# 2nd_layer.net
KiCad netlist of a schematic drawn in EAGLE
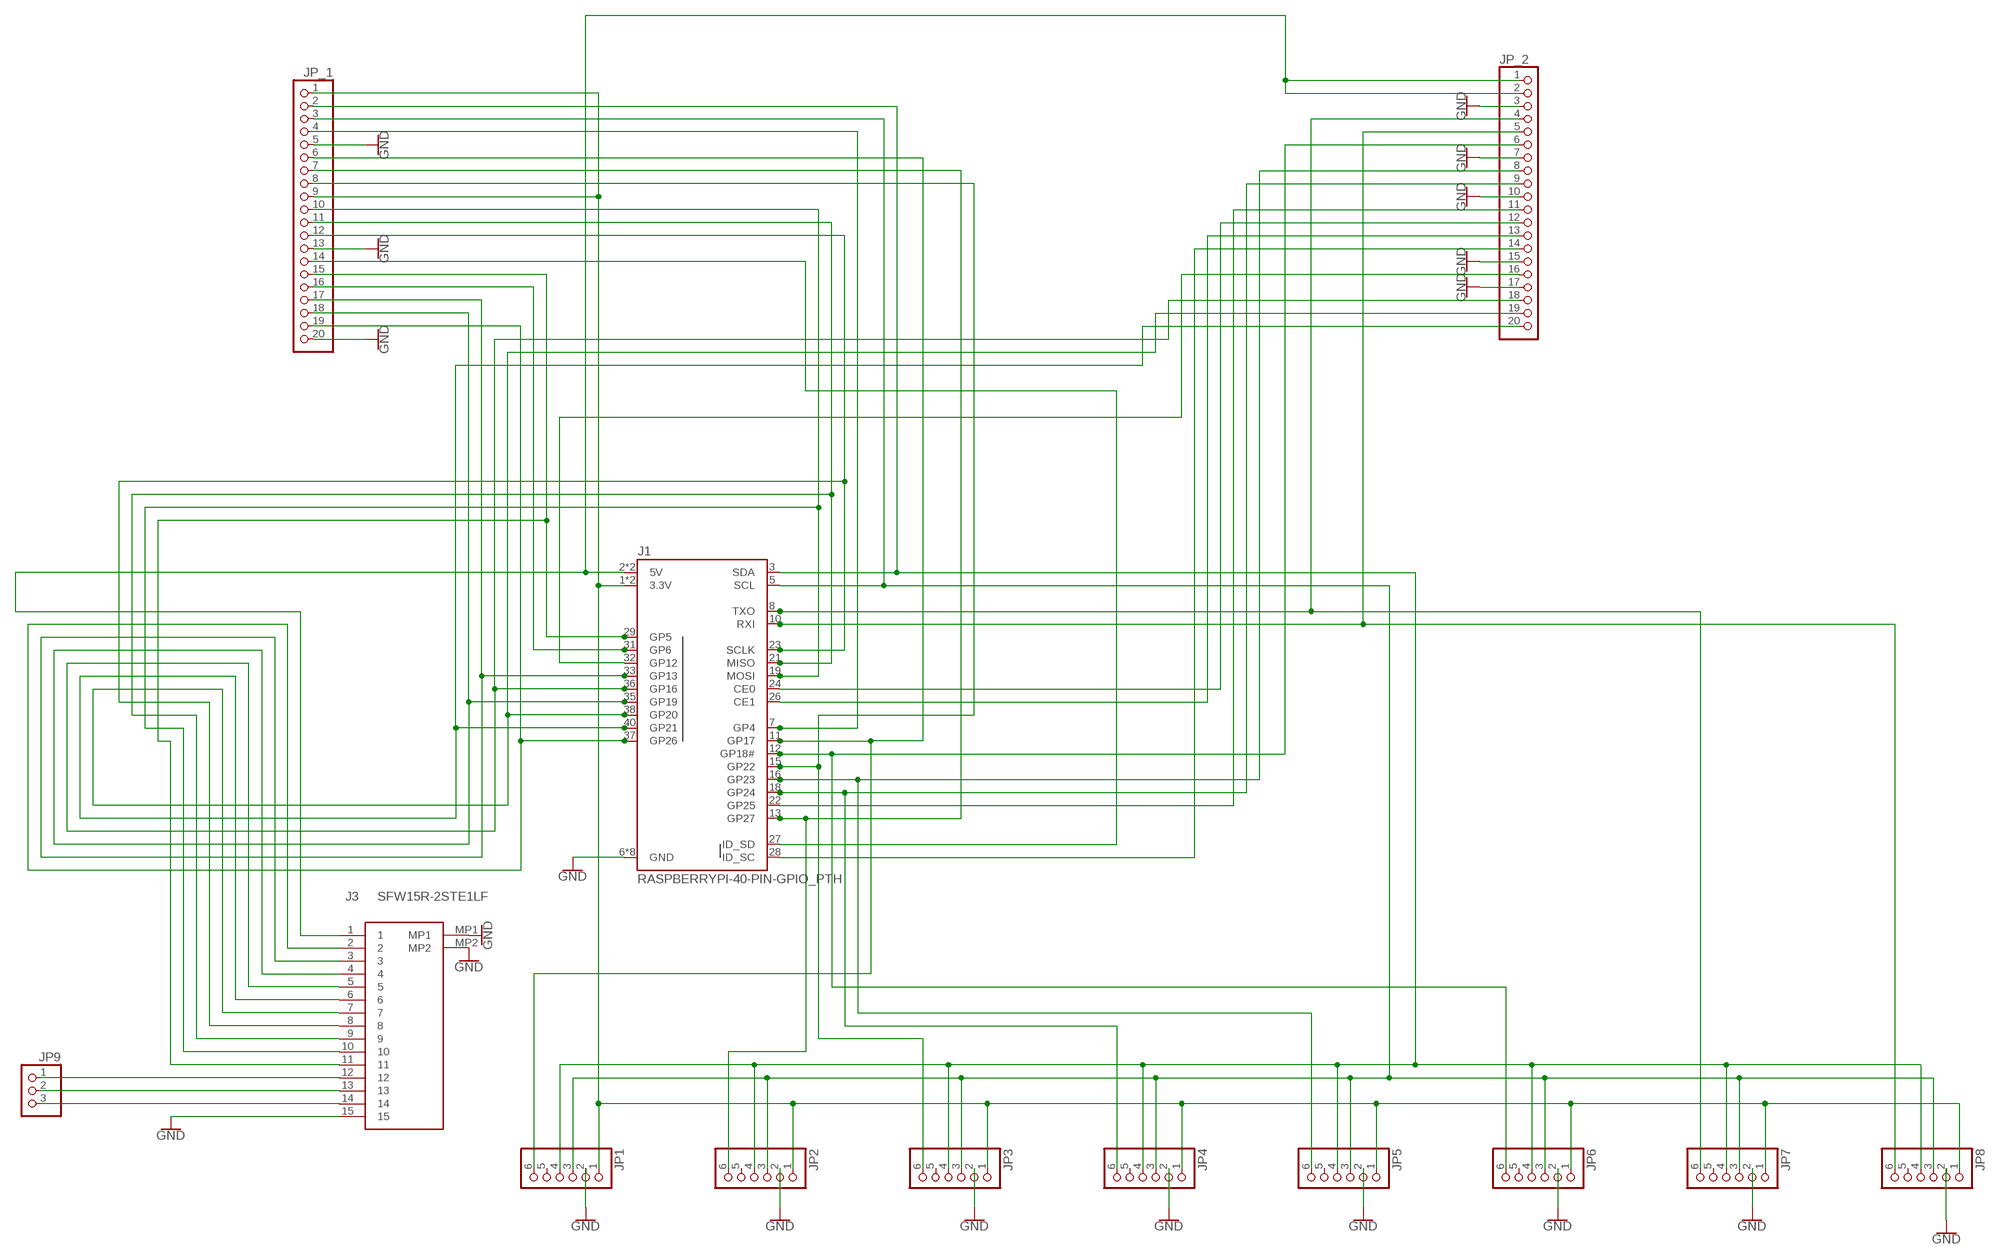
[diagram p0: schematic, sheet 1]

(export (version "E")
  (design (tool "Eeschema 10.0.6"))
  (components
    (comp (ref "J1")
      (value "RASPBERRYPI-40-PIN-GPIO_PTH")
      (footprint "eagle-import:2X20_SHROUDED")
      (libsource (lib "eagle-import") (part "RASPBERRYPI-40-PIN-GPIO_PTH"))
    )
    (comp (ref "J3")
      (value "SFW15R-2STE1LF")
      (footprint "eagle-import:SFW15R2STE1LF")
      (libsource (lib "eagle-import") (part "SFW15R-2STE1LF"))
    )
    (comp (ref "JP1")
      (value "PINHD-1X6")
      (footprint "eagle-import:1X06")
      (libsource (lib "eagle-import") (part "PINHD-1X6"))
    )
    (comp (ref "JP2")
      (value "PINHD-1X6")
      (footprint "eagle-import:1X06")
      (libsource (lib "eagle-import") (part "PINHD-1X6"))
    )
    (comp (ref "JP3")
      (value "PINHD-1X6")
      (footprint "eagle-import:1X06")
      (libsource (lib "eagle-import") (part "PINHD-1X6"))
    )
    (comp (ref "JP4")
      (value "PINHD-1X6")
      (footprint "eagle-import:1X06")
      (libsource (lib "eagle-import") (part "PINHD-1X6"))
    )
    (comp (ref "JP5")
      (value "PINHD-1X6")
      (footprint "eagle-import:1X06")
      (libsource (lib "eagle-import") (part "PINHD-1X6"))
    )
    (comp (ref "JP6")
      (value "PINHD-1X6")
      (footprint "eagle-import:1X06")
      (libsource (lib "eagle-import") (part "PINHD-1X6"))
    )
    (comp (ref "JP7")
      (value "PINHD-1X6")
      (footprint "eagle-import:1X06")
      (libsource (lib "eagle-import") (part "PINHD-1X6"))
    )
    (comp (ref "JP8")
      (value "PINHD-1X6")
      (footprint "eagle-import:1X06")
      (libsource (lib "eagle-import") (part "PINHD-1X6"))
    )
    (comp (ref "JP9")
      (value "PINHD-1X3")
      (footprint "eagle-import:1X03")
      (libsource (lib "eagle-import") (part "PINHD-1X3"))
    )
    (comp (ref "JP_1")
      (value "PINHD-1X20")
      (footprint "eagle-import:1X20")
      (libsource (lib "eagle-import") (part "PINHD-1X20"))
    )
    (comp (ref "JP_2")
      (value "PINHD-1X20")
      (footprint "eagle-import:1X20")
      (libsource (lib "eagle-import") (part "PINHD-1X20"))
    )
  )
  (nets
    (net (code "1") (name "GND") (class "Default")
      (node (ref "J1") (pin "14") (pinfunction "GND_14") (pintype "power_in"))
      (node (ref "J1") (pin "20") (pinfunction "GND_20") (pintype "power_in"))
      (node (ref "J1") (pin "25") (pinfunction "GND_25") (pintype "power_in"))
      (node (ref "J1") (pin "30") (pinfunction "GND_30") (pintype "power_in"))
      (node (ref "J1") (pin "34") (pinfunction "GND_34") (pintype "power_in"))
      (node (ref "J1") (pin "39") (pinfunction "GND_39") (pintype "power_in"))
      (node (ref "J1") (pin "6") (pinfunction "GND_6") (pintype "power_in"))
      (node (ref "J1") (pin "9") (pinfunction "GND_9") (pintype "power_in"))
      (node (ref "J3") (pin "15") (pinfunction "15_15") (pintype "bidirectional"))
      (node (ref "J3") (pin "MP1") (pinfunction "MP1_MP1") (pintype "bidirectional"))
      (node (ref "J3") (pin "MP2") (pinfunction "MP2_MP2") (pintype "bidirectional"))
      (node (ref "JP1") (pin "2") (pinfunction "2_2") (pintype "passive"))
      (node (ref "JP2") (pin "2") (pinfunction "2_2") (pintype "passive"))
      (node (ref "JP3") (pin "2") (pinfunction "2_2") (pintype "passive"))
      (node (ref "JP4") (pin "2") (pinfunction "2_2") (pintype "passive"))
      (node (ref "JP5") (pin "2") (pinfunction "2_2") (pintype "passive"))
      (node (ref "JP6") (pin "2") (pinfunction "2_2") (pintype "passive"))
      (node (ref "JP7") (pin "2") (pinfunction "2_2") (pintype "passive"))
      (node (ref "JP8") (pin "2") (pinfunction "2_2") (pintype "passive"))
      (node (ref "JP_1") (pin "13") (pinfunction "13_13") (pintype "passive"))
      (node (ref "JP_1") (pin "20") (pinfunction "20_20") (pintype "passive"))
      (node (ref "JP_1") (pin "5") (pinfunction "5_5") (pintype "passive"))
      (node (ref "JP_2") (pin "10") (pinfunction "10_10") (pintype "passive"))
      (node (ref "JP_2") (pin "15") (pinfunction "15_15") (pintype "passive"))
      (node (ref "JP_2") (pin "17") (pinfunction "17_17") (pintype "passive"))
      (node (ref "JP_2") (pin "3") (pinfunction "3_3") (pintype "passive"))
      (node (ref "JP_2") (pin "7") (pinfunction "7_7") (pintype "passive"))
    )
    (net (code "2") (name "Net-(J1-3.3V-Pad1)") (class "Default")
      (node (ref "J1") (pin "1") (pinfunction "3.3V_1") (pintype "power_in"))
      (node (ref "J1") (pin "17") (pinfunction "3.3V_17") (pintype "power_in"))
      (node (ref "JP1") (pin "1") (pinfunction "1_1") (pintype "passive"))
      (node (ref "JP2") (pin "1") (pinfunction "1_1") (pintype "passive"))
      (node (ref "JP3") (pin "1") (pinfunction "1_1") (pintype "passive"))
      (node (ref "JP4") (pin "1") (pinfunction "1_1") (pintype "passive"))
      (node (ref "JP5") (pin "1") (pinfunction "1_1") (pintype "passive"))
      (node (ref "JP6") (pin "1") (pinfunction "1_1") (pintype "passive"))
      (node (ref "JP7") (pin "1") (pinfunction "1_1") (pintype "passive"))
      (node (ref "JP8") (pin "1") (pinfunction "1_1") (pintype "passive"))
      (node (ref "JP_1") (pin "1") (pinfunction "1_1") (pintype "passive"))
      (node (ref "JP_1") (pin "9") (pinfunction "9_9") (pintype "passive"))
    )
    (net (code "3") (name "Net-(J1-5V-Pad2)") (class "Default")
      (node (ref "J1") (pin "2") (pinfunction "5V_2") (pintype "power_in"))
      (node (ref "J1") (pin "4") (pinfunction "5V_4") (pintype "power_in"))
      (node (ref "J3") (pin "1") (pinfunction "1_1") (pintype "bidirectional"))
      (node (ref "JP_2") (pin "1") (pinfunction "1_1") (pintype "passive"))
      (node (ref "JP_2") (pin "2") (pinfunction "2_2") (pintype "passive"))
    )
    (net (code "4") (name "Net-(J1-CE0)") (class "Default")
      (node (ref "J1") (pin "24") (pinfunction "CE0_24") (pintype "output"))
      (node (ref "JP_2") (pin "12") (pinfunction "12_12") (pintype "passive"))
    )
    (net (code "5") (name "Net-(J1-CE1)") (class "Default")
      (node (ref "J1") (pin "26") (pinfunction "CE1_26") (pintype "output"))
      (node (ref "JP_2") (pin "13") (pinfunction "13_13") (pintype "passive"))
    )
    (net (code "6") (name "Net-(J1-GP4)") (class "Default")
      (node (ref "J1") (pin "7") (pinfunction "GP4_7") (pintype "bidirectional"))
      (node (ref "JP_1") (pin "4") (pinfunction "4_4") (pintype "passive"))
    )
    (net (code "7") (name "Net-(J1-GP5)") (class "Default")
      (node (ref "J1") (pin "29") (pinfunction "GP5_29") (pintype "bidirectional"))
      (node (ref "J3") (pin "11") (pinfunction "11_11") (pintype "bidirectional"))
      (node (ref "JP_1") (pin "15") (pinfunction "15_15") (pintype "passive"))
    )
    (net (code "8") (name "Net-(J1-GP6)") (class "Default")
      (node (ref "J1") (pin "31") (pinfunction "GP6_31") (pintype "bidirectional"))
      (node (ref "JP_1") (pin "16") (pinfunction "16_16") (pintype "passive"))
    )
    (net (code "9") (name "Net-(J1-GP12)") (class "Default")
      (node (ref "J1") (pin "32") (pinfunction "GP12_32") (pintype "bidirectional"))
      (node (ref "JP_2") (pin "16") (pinfunction "16_16") (pintype "passive"))
    )
    (net (code "10") (name "Net-(J1-GP13)") (class "Default")
      (node (ref "J1") (pin "33") (pinfunction "GP13_33") (pintype "bidirectional"))
      (node (ref "J3") (pin "3") (pinfunction "3_3") (pintype "bidirectional"))
      (node (ref "JP_1") (pin "17") (pinfunction "17_17") (pintype "passive"))
    )
    (net (code "11") (name "Net-(J1-GP16)") (class "Default")
      (node (ref "J1") (pin "36") (pinfunction "GP16_36") (pintype "bidirectional"))
      (node (ref "J3") (pin "5") (pinfunction "5_5") (pintype "bidirectional"))
      (node (ref "JP_2") (pin "18") (pinfunction "18_18") (pintype "passive"))
    )
    (net (code "12") (name "Net-(J1-GP17)") (class "Default")
      (node (ref "J1") (pin "11") (pinfunction "GP17_11") (pintype "bidirectional"))
      (node (ref "JP1") (pin "6") (pinfunction "6_6") (pintype "passive"))
      (node (ref "JP_1") (pin "6") (pinfunction "6_6") (pintype "passive"))
    )
    (net (code "13") (name "Net-(J1-GP18#)") (class "Default")
      (node (ref "J1") (pin "12") (pinfunction "GP18#_12") (pintype "bidirectional"))
      (node (ref "JP6") (pin "6") (pinfunction "6_6") (pintype "passive"))
      (node (ref "JP_2") (pin "6") (pinfunction "6_6") (pintype "passive"))
    )
    (net (code "14") (name "Net-(J1-GP19)") (class "Default")
      (node (ref "J1") (pin "35") (pinfunction "GP19_35") (pintype "bidirectional"))
      (node (ref "J3") (pin "4") (pinfunction "4_4") (pintype "bidirectional"))
      (node (ref "JP_1") (pin "18") (pinfunction "18_18") (pintype "passive"))
    )
    (net (code "15") (name "Net-(J1-GP20)") (class "Default")
      (node (ref "J1") (pin "38") (pinfunction "GP20_38") (pintype "bidirectional"))
      (node (ref "J3") (pin "7") (pinfunction "7_7") (pintype "bidirectional"))
      (node (ref "JP_2") (pin "19") (pinfunction "19_19") (pintype "passive"))
    )
    (net (code "16") (name "Net-(J1-GP21)") (class "Default")
      (node (ref "J1") (pin "40") (pinfunction "GP21_40") (pintype "bidirectional"))
      (node (ref "J3") (pin "6") (pinfunction "6_6") (pintype "bidirectional"))
      (node (ref "JP_2") (pin "20") (pinfunction "20_20") (pintype "passive"))
    )
    (net (code "17") (name "Net-(J1-GP22)") (class "Default")
      (node (ref "J1") (pin "15") (pinfunction "GP22_15") (pintype "bidirectional"))
      (node (ref "JP3") (pin "6") (pinfunction "6_6") (pintype "passive"))
      (node (ref "JP_1") (pin "8") (pinfunction "8_8") (pintype "passive"))
    )
    (net (code "18") (name "Net-(J1-GP23)") (class "Default")
      (node (ref "J1") (pin "16") (pinfunction "GP23_16") (pintype "bidirectional"))
      (node (ref "JP5") (pin "6") (pinfunction "6_6") (pintype "passive"))
      (node (ref "JP_2") (pin "8") (pinfunction "8_8") (pintype "passive"))
    )
    (net (code "19") (name "Net-(J1-GP24)") (class "Default")
      (node (ref "J1") (pin "18") (pinfunction "GP24_18") (pintype "bidirectional"))
      (node (ref "JP4") (pin "6") (pinfunction "6_6") (pintype "passive"))
      (node (ref "JP_2") (pin "9") (pinfunction "9_9") (pintype "passive"))
    )
    (net (code "20") (name "Net-(J1-GP25)") (class "Default")
      (node (ref "J1") (pin "22") (pinfunction "GP25_22") (pintype "bidirectional"))
      (node (ref "JP_2") (pin "11") (pinfunction "11_11") (pintype "passive"))
    )
    (net (code "21") (name "Net-(J1-GP26)") (class "Default")
      (node (ref "J1") (pin "37") (pinfunction "GP26_37") (pintype "bidirectional"))
      (node (ref "J3") (pin "2") (pinfunction "2_2") (pintype "bidirectional"))
      (node (ref "JP_1") (pin "19") (pinfunction "19_19") (pintype "passive"))
    )
    (net (code "22") (name "Net-(J1-GP27)") (class "Default")
      (node (ref "J1") (pin "13") (pinfunction "GP27_13") (pintype "bidirectional"))
      (node (ref "JP2") (pin "6") (pinfunction "6_6") (pintype "passive"))
      (node (ref "JP_1") (pin "7") (pinfunction "7_7") (pintype "passive"))
    )
    (net (code "23") (name "Net-(J1-ID_SC)") (class "Default")
      (node (ref "J1") (pin "28") (pinfunction "ID_SC_28") (pintype "bidirectional"))
      (node (ref "JP_2") (pin "14") (pinfunction "14_14") (pintype "passive"))
    )
    (net (code "24") (name "Net-(J1-ID_SD)") (class "Default")
      (node (ref "J1") (pin "27") (pinfunction "ID_SD_27") (pintype "bidirectional"))
      (node (ref "JP_1") (pin "14") (pinfunction "14_14") (pintype "passive"))
    )
    (net (code "25") (name "Net-(J1-MISO)") (class "Default")
      (node (ref "J1") (pin "21") (pinfunction "MISO_21") (pintype "input"))
      (node (ref "J3") (pin "9") (pinfunction "9_9") (pintype "bidirectional"))
      (node (ref "JP_1") (pin "11") (pinfunction "11_11") (pintype "passive"))
    )
    (net (code "26") (name "Net-(J1-MOSI)") (class "Default")
      (node (ref "J1") (pin "19") (pinfunction "MOSI_19") (pintype "output"))
      (node (ref "J3") (pin "10") (pinfunction "10_10") (pintype "bidirectional"))
      (node (ref "JP_1") (pin "10") (pinfunction "10_10") (pintype "passive"))
    )
    (net (code "27") (name "Net-(J1-RXI)") (class "Default")
      (node (ref "J1") (pin "10") (pinfunction "RXI_10") (pintype "input"))
      (node (ref "JP8") (pin "6") (pinfunction "6_6") (pintype "passive"))
      (node (ref "JP_2") (pin "5") (pinfunction "5_5") (pintype "passive"))
    )
    (net (code "28") (name "Net-(J1-SCL)") (class "Default")
      (node (ref "J1") (pin "5") (pinfunction "SCL_5") (pintype "bidirectional"))
      (node (ref "JP1") (pin "3") (pinfunction "3_3") (pintype "passive"))
      (node (ref "JP2") (pin "3") (pinfunction "3_3") (pintype "passive"))
      (node (ref "JP3") (pin "3") (pinfunction "3_3") (pintype "passive"))
      (node (ref "JP4") (pin "3") (pinfunction "3_3") (pintype "passive"))
      (node (ref "JP5") (pin "3") (pinfunction "3_3") (pintype "passive"))
      (node (ref "JP6") (pin "3") (pinfunction "3_3") (pintype "passive"))
      (node (ref "JP7") (pin "3") (pinfunction "3_3") (pintype "passive"))
      (node (ref "JP8") (pin "3") (pinfunction "3_3") (pintype "passive"))
      (node (ref "JP_1") (pin "3") (pinfunction "3_3") (pintype "passive"))
    )
    (net (code "29") (name "Net-(J1-SCLK)") (class "Default")
      (node (ref "J1") (pin "23") (pinfunction "SCLK_23") (pintype "output"))
      (node (ref "J3") (pin "8") (pinfunction "8_8") (pintype "bidirectional"))
      (node (ref "JP_1") (pin "12") (pinfunction "12_12") (pintype "passive"))
    )
    (net (code "30") (name "Net-(J1-SDA)") (class "Default")
      (node (ref "J1") (pin "3") (pinfunction "SDA_3") (pintype "bidirectional"))
      (node (ref "JP1") (pin "4") (pinfunction "4_4") (pintype "passive"))
      (node (ref "JP2") (pin "4") (pinfunction "4_4") (pintype "passive"))
      (node (ref "JP3") (pin "4") (pinfunction "4_4") (pintype "passive"))
      (node (ref "JP4") (pin "4") (pinfunction "4_4") (pintype "passive"))
      (node (ref "JP5") (pin "4") (pinfunction "4_4") (pintype "passive"))
      (node (ref "JP6") (pin "4") (pinfunction "4_4") (pintype "passive"))
      (node (ref "JP7") (pin "4") (pinfunction "4_4") (pintype "passive"))
      (node (ref "JP8") (pin "4") (pinfunction "4_4") (pintype "passive"))
      (node (ref "JP_1") (pin "2") (pinfunction "2_2") (pintype "passive"))
    )
    (net (code "31") (name "Net-(J1-TXO)") (class "Default")
      (node (ref "J1") (pin "8") (pinfunction "TXO_8") (pintype "output"))
      (node (ref "JP7") (pin "6") (pinfunction "6_6") (pintype "passive"))
      (node (ref "JP_2") (pin "4") (pinfunction "4_4") (pintype "passive"))
    )
    (net (code "32") (name "Net-(J3-Pad12)") (class "Default")
      (node (ref "J3") (pin "12") (pinfunction "12_12") (pintype "bidirectional"))
      (node (ref "JP9") (pin "1") (pinfunction "1_1") (pintype "passive"))
    )
    (net (code "33") (name "Net-(J3-Pad13)") (class "Default")
      (node (ref "J3") (pin "13") (pinfunction "13_13") (pintype "bidirectional"))
      (node (ref "JP9") (pin "2") (pinfunction "2_2") (pintype "passive"))
    )
    (net (code "34") (name "Net-(J3-Pad14)") (class "Default")
      (node (ref "J3") (pin "14") (pinfunction "14_14") (pintype "bidirectional"))
      (node (ref "JP9") (pin "3") (pinfunction "3_3") (pintype "passive"))
    )
    (net (code "35") (name "unconnected-(JP1-Pad5)") (class "Default")
      (node (ref "JP1") (pin "5") (pinfunction "5_5") (pintype "passive"))
    )
    (net (code "36") (name "unconnected-(JP2-Pad5)") (class "Default")
      (node (ref "JP2") (pin "5") (pinfunction "5_5") (pintype "passive"))
    )
    (net (code "37") (name "unconnected-(JP3-Pad5)") (class "Default")
      (node (ref "JP3") (pin "5") (pinfunction "5_5") (pintype "passive"))
    )
    (net (code "38") (name "unconnected-(JP4-Pad5)") (class "Default")
      (node (ref "JP4") (pin "5") (pinfunction "5_5") (pintype "passive"))
    )
    (net (code "39") (name "unconnected-(JP5-Pad5)") (class "Default")
      (node (ref "JP5") (pin "5") (pinfunction "5_5") (pintype "passive"))
    )
    (net (code "40") (name "unconnected-(JP6-Pad5)") (class "Default")
      (node (ref "JP6") (pin "5") (pinfunction "5_5") (pintype "passive"))
    )
    (net (code "41") (name "unconnected-(JP7-Pad5)") (class "Default")
      (node (ref "JP7") (pin "5") (pinfunction "5_5") (pintype "passive"))
    )
    (net (code "42") (name "unconnected-(JP8-Pad5)") (class "Default")
      (node (ref "JP8") (pin "5") (pinfunction "5_5") (pintype "passive"))
    )
  )
)
